# 13_LMS3_Power.net
KiCad netlist of a schematic drawn in Altium Designer
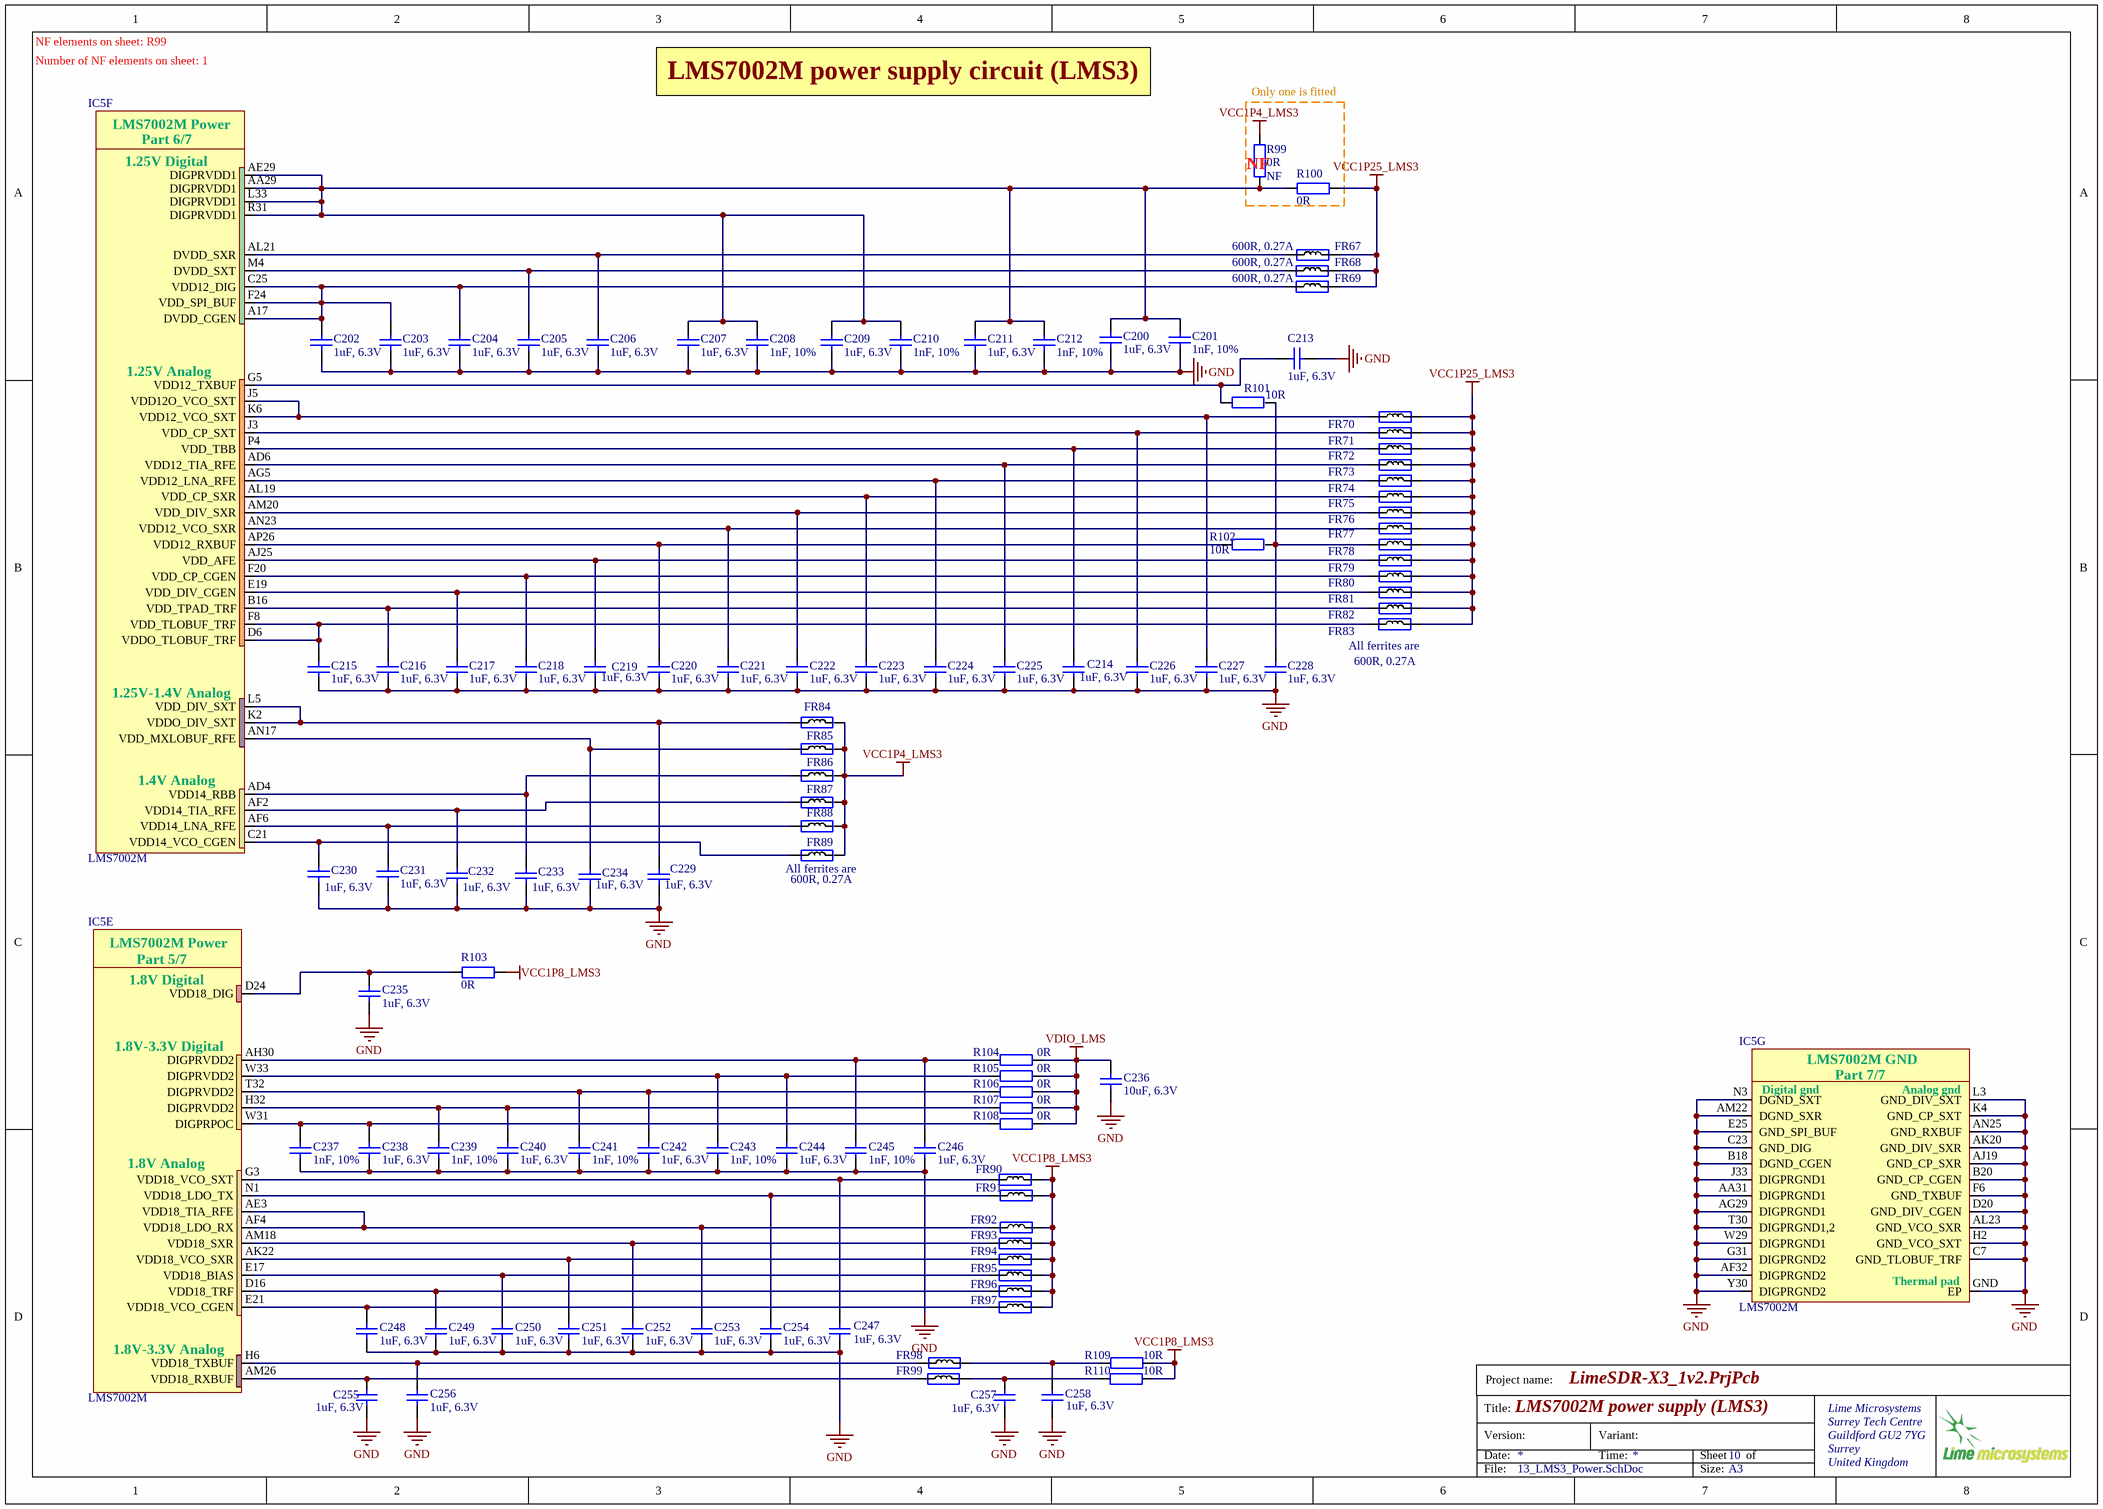
[diagram p0: 13_LMS3_Power.SchDoc]

(export (version "E")
  (design (tool "Eeschema 10.0.6"))
  (components
    (comp (ref "C200")
      (value "1uF, 6.3V")
      (footprint "CAP0201")
      (fields (field (name "TOLERANCE") "±20%") (field (name "MANUFACTURER") "TDK Corporation"))
      (libsource (lib "") (part "Cap_0402_2"))
    )
    (comp (ref "C201")
      (value "1nF, 10%")
      (footprint "CAP0201")
      (fields (field (name "TOLERANCE") "±10%") (field (name "MANUFACTURER") "TDK Corporation"))
      (libsource (lib "") (part "Cap_0402_2"))
    )
    (comp (ref "C202")
      (value "1uF, 6.3V")
      (footprint "CAP0201")
      (fields (field (name "TOLERANCE") "±20%") (field (name "MANUFACTURER") "TDK Corporation"))
      (libsource (lib "") (part "Cap_0402_1"))
    )
    (comp (ref "C203")
      (value "1uF, 6.3V")
      (footprint "CAP0201")
      (fields (field (name "TOLERANCE") "±20%") (field (name "MANUFACTURER") "TDK Corporation"))
      (libsource (lib "") (part "Cap_0402_1"))
    )
    (comp (ref "C204")
      (value "1uF, 6.3V")
      (footprint "CAP0201")
      (fields (field (name "TOLERANCE") "±20%") (field (name "MANUFACTURER") "TDK Corporation"))
      (libsource (lib "") (part "Cap_0402_1"))
    )
    (comp (ref "C205")
      (value "1uF, 6.3V")
      (footprint "CAP0201")
      (fields (field (name "TOLERANCE") "±20%") (field (name "MANUFACTURER") "TDK Corporation"))
      (libsource (lib "") (part "Cap_0402_2"))
    )
    (comp (ref "C206")
      (value "1uF, 6.3V")
      (footprint "CAP0201")
      (fields (field (name "TOLERANCE") "±20%") (field (name "MANUFACTURER") "TDK Corporation"))
      (libsource (lib "") (part "Cap_0402_1"))
    )
    (comp (ref "C207")
      (value "1uF, 6.3V")
      (footprint "CAP0201")
      (fields (field (name "TOLERANCE") "±20%") (field (name "MANUFACTURER") "TDK Corporation"))
      (libsource (lib "") (part "Cap_0402_2"))
    )
    (comp (ref "C208")
      (value "1nF, 10%")
      (footprint "CAP0201")
      (fields (field (name "TOLERANCE") "±10%") (field (name "MANUFACTURER") "TDK Corporation"))
      (libsource (lib "") (part "Cap_0402_2"))
    )
    (comp (ref "C209")
      (value "1uF, 6.3V")
      (footprint "CAP0201")
      (fields (field (name "TOLERANCE") "±20%") (field (name "MANUFACTURER") "TDK Corporation"))
      (libsource (lib "") (part "Cap_0402_2"))
    )
    (comp (ref "C210")
      (value "1nF, 10%")
      (footprint "CAP0201")
      (fields (field (name "TOLERANCE") "±10%") (field (name "MANUFACTURER") "TDK Corporation"))
      (libsource (lib "") (part "Cap_0402_2"))
    )
    (comp (ref "C211")
      (value "1uF, 6.3V")
      (footprint "CAP0201")
      (fields (field (name "TOLERANCE") "±20%") (field (name "MANUFACTURER") "TDK Corporation"))
      (libsource (lib "") (part "Cap_0402_2"))
    )
    (comp (ref "C212")
      (value "1nF, 10%")
      (footprint "CAP0201")
      (fields (field (name "TOLERANCE") "±10%") (field (name "MANUFACTURER") "TDK Corporation"))
      (libsource (lib "") (part "Cap_0402_2"))
    )
    (comp (ref "C213")
      (value "1uF, 6.3V")
      (footprint "CAP0201")
      (fields (field (name "TOLERANCE") "±20%") (field (name "MANUFACTURER") "TDK Corporation"))
      (libsource (lib "") (part "Cap_0402_4"))
    )
    (comp (ref "C214")
      (value "1uF, 6.3V")
      (footprint "CAP0201")
      (fields (field (name "TOLERANCE") "±20%") (field (name "MANUFACTURER") "TDK Corporation"))
      (libsource (lib "") (part "Cap_0402_1"))
    )
    (comp (ref "C215")
      (value "1uF, 6.3V")
      (footprint "CAP0201")
      (fields (field (name "TOLERANCE") "±20%") (field (name "MANUFACTURER") "TDK Corporation"))
      (libsource (lib "") (part "Cap_0402_1"))
    )
    (comp (ref "C216")
      (value "1uF, 6.3V")
      (footprint "CAP0201")
      (fields (field (name "TOLERANCE") "±20%") (field (name "MANUFACTURER") "TDK Corporation"))
      (libsource (lib "") (part "Cap_0402_1"))
    )
    (comp (ref "C217")
      (value "1uF, 6.3V")
      (footprint "CAP0201")
      (fields (field (name "TOLERANCE") "±20%") (field (name "MANUFACTURER") "TDK Corporation"))
      (libsource (lib "") (part "Cap_0402_1"))
    )
    (comp (ref "C218")
      (value "1uF, 6.3V")
      (footprint "CAP0201")
      (fields (field (name "TOLERANCE") "±20%") (field (name "MANUFACTURER") "TDK Corporation"))
      (libsource (lib "") (part "Cap_0402_2"))
    )
    (comp (ref "C219")
      (value "1uF, 6.3V")
      (footprint "CAP0201")
      (fields (field (name "TOLERANCE") "±20%") (field (name "MANUFACTURER") "TDK Corporation"))
      (libsource (lib "") (part "Cap_0402_1"))
    )
    (comp (ref "C220")
      (value "1uF, 6.3V")
      (footprint "CAP0201")
      (fields (field (name "TOLERANCE") "±20%") (field (name "MANUFACTURER") "TDK Corporation"))
      (libsource (lib "") (part "Cap_0402_1"))
    )
    (comp (ref "C221")
      (value "1uF, 6.3V")
      (footprint "CAP0201")
      (fields (field (name "TOLERANCE") "±20%") (field (name "MANUFACTURER") "TDK Corporation"))
      (libsource (lib "") (part "Cap_0402_1"))
    )
    (comp (ref "C222")
      (value "1uF, 6.3V")
      (footprint "CAP0201")
      (fields (field (name "TOLERANCE") "±20%") (field (name "MANUFACTURER") "TDK Corporation"))
      (libsource (lib "") (part "Cap_0402_1"))
    )
    (comp (ref "C223")
      (value "1uF, 6.3V")
      (footprint "CAP0201")
      (fields (field (name "TOLERANCE") "±20%") (field (name "MANUFACTURER") "TDK Corporation"))
      (libsource (lib "") (part "Cap_0402_1"))
    )
    (comp (ref "C224")
      (value "1uF, 6.3V")
      (footprint "CAP0201")
      (fields (field (name "TOLERANCE") "±20%") (field (name "MANUFACTURER") "TDK Corporation"))
      (libsource (lib "") (part "Cap_0402_1"))
    )
    (comp (ref "C225")
      (value "1uF, 6.3V")
      (footprint "CAP0201")
      (fields (field (name "TOLERANCE") "±20%") (field (name "MANUFACTURER") "TDK Corporation"))
      (libsource (lib "") (part "Cap_0402_2"))
    )
    (comp (ref "C226")
      (value "1uF, 6.3V")
      (footprint "CAP0201")
      (fields (field (name "TOLERANCE") "±20%") (field (name "MANUFACTURER") "TDK Corporation"))
      (libsource (lib "") (part "Cap_0402_1"))
    )
    (comp (ref "C227")
      (value "1uF, 6.3V")
      (footprint "CAP0201")
      (fields (field (name "TOLERANCE") "±20%") (field (name "MANUFACTURER") "TDK Corporation"))
      (libsource (lib "") (part "Cap_0402_2"))
    )
    (comp (ref "C228")
      (value "1uF, 6.3V")
      (footprint "CAP0201")
      (fields (field (name "TOLERANCE") "±20%") (field (name "MANUFACTURER") "TDK Corporation"))
      (libsource (lib "") (part "Cap_0402_2"))
    )
    (comp (ref "C229")
      (value "1uF, 6.3V")
      (footprint "CAP0201")
      (fields (field (name "TOLERANCE") "±20%") (field (name "MANUFACTURER") "TDK Corporation"))
      (libsource (lib "") (part "Cap_0402_1"))
    )
    (comp (ref "C230")
      (value "1uF, 6.3V")
      (footprint "CAP0201")
      (fields (field (name "TOLERANCE") "±20%") (field (name "MANUFACTURER") "TDK Corporation"))
      (libsource (lib "") (part "Cap_0402_1"))
    )
    (comp (ref "C231")
      (value "1uF, 6.3V")
      (footprint "CAP0201")
      (fields (field (name "TOLERANCE") "±20%") (field (name "MANUFACTURER") "TDK Corporation"))
      (libsource (lib "") (part "Cap_0402_1"))
    )
    (comp (ref "C232")
      (value "1uF, 6.3V")
      (footprint "CAP0201")
      (fields (field (name "TOLERANCE") "±20%") (field (name "MANUFACTURER") "TDK Corporation"))
      (libsource (lib "") (part "Cap_0402_3"))
    )
    (comp (ref "C233")
      (value "1uF, 6.3V")
      (footprint "CAP0201")
      (fields (field (name "TOLERANCE") "±20%") (field (name "MANUFACTURER") "TDK Corporation"))
      (libsource (lib "") (part "Cap_0402_3"))
    )
    (comp (ref "C234")
      (value "1uF, 6.3V")
      (footprint "CAP0201")
      (fields (field (name "TOLERANCE") "±20%") (field (name "MANUFACTURER") "TDK Corporation"))
      (libsource (lib "") (part "Cap_0402_1"))
    )
    (comp (ref "C235")
      (value "1uF, 6.3V")
      (footprint "CAP0201")
      (fields (field (name "TOLERANCE") "±20%") (field (name "MANUFACTURER") "TDK Corporation"))
      (libsource (lib "LimeMicroAltiumLib_schLib") (part "Cap_0402"))
    )
    (comp (ref "C236")
      (value "10uF, 6.3V")
      (footprint "CAP0603")
      (fields (field (name "TOLERANCE") "±20%") (field (name "MANUFACTURER") "Yageo"))
      (libsource (lib "LimeFPGAboard_schLib") (part "Cap_0603"))
    )
    (comp (ref "C237")
      (value "1nF, 10%")
      (footprint "CAP0201")
      (fields (field (name "TOLERANCE") "±10%") (field (name "MANUFACTURER") "TDK Corporation"))
      (libsource (lib "LimeMicroAltiumLib_schLib") (part "Cap_0402"))
    )
    (comp (ref "C238")
      (value "1uF, 6.3V")
      (footprint "CAP0201")
      (fields (field (name "TOLERANCE") "±20%") (field (name "MANUFACTURER") "TDK Corporation"))
      (libsource (lib "LimeMicroAltiumLib_schLib") (part "Cap_0402"))
    )
    (comp (ref "C239")
      (value "1nF, 10%")
      (footprint "CAP0201")
      (fields (field (name "TOLERANCE") "±10%") (field (name "MANUFACTURER") "TDK Corporation"))
      (libsource (lib "LimeMicroAltiumLib_schLib") (part "Cap_0402"))
    )
    (comp (ref "C240")
      (value "1uF, 6.3V")
      (footprint "CAP0201")
      (fields (field (name "TOLERANCE") "±20%") (field (name "MANUFACTURER") "TDK Corporation"))
      (libsource (lib "LimeMicroAltiumLib_schLib") (part "Cap_0402"))
    )
    (comp (ref "C241")
      (value "1nF, 10%")
      (footprint "CAP0201")
      (fields (field (name "TOLERANCE") "±10%") (field (name "MANUFACTURER") "TDK Corporation"))
      (libsource (lib "LimeMicroAltiumLib_schLib") (part "Cap_0402"))
    )
    (comp (ref "C242")
      (value "1uF, 6.3V")
      (footprint "CAP0201")
      (fields (field (name "TOLERANCE") "±20%") (field (name "MANUFACTURER") "TDK Corporation"))
      (libsource (lib "LimeMicroAltiumLib_schLib") (part "Cap_0402"))
    )
    (comp (ref "C243")
      (value "1nF, 10%")
      (footprint "CAP0201")
      (fields (field (name "TOLERANCE") "±10%") (field (name "MANUFACTURER") "TDK Corporation"))
      (libsource (lib "LimeMicroAltiumLib_schLib") (part "Cap_0402"))
    )
    (comp (ref "C244")
      (value "1uF, 6.3V")
      (footprint "CAP0201")
      (fields (field (name "TOLERANCE") "±20%") (field (name "MANUFACTURER") "TDK Corporation"))
      (libsource (lib "LimeMicroAltiumLib_schLib") (part "Cap_0402"))
    )
    (comp (ref "C245")
      (value "1nF, 10%")
      (footprint "CAP0201")
      (fields (field (name "TOLERANCE") "±10%") (field (name "MANUFACTURER") "TDK Corporation"))
      (libsource (lib "LimeMicroAltiumLib_schLib") (part "Cap_0402"))
    )
    (comp (ref "C246")
      (value "1uF, 6.3V")
      (footprint "CAP0201")
      (fields (field (name "TOLERANCE") "±20%") (field (name "MANUFACTURER") "TDK Corporation"))
      (libsource (lib "LimeMicroAltiumLib_schLib") (part "Cap_0402"))
    )
    (comp (ref "C247")
      (value "1uF, 6.3V")
      (footprint "CAP0201")
      (fields (field (name "TOLERANCE") "±20%") (field (name "MANUFACTURER") "TDK Corporation"))
      (libsource (lib "LimeMicroAltiumLib_schLib") (part "Cap_0402"))
    )
    (comp (ref "C248")
      (value "1uF, 6.3V")
      (footprint "CAP0201")
      (fields (field (name "TOLERANCE") "±20%") (field (name "MANUFACTURER") "TDK Corporation"))
      (libsource (lib "LimeMicroAltiumLib_schLib") (part "Cap_0402"))
    )
    (comp (ref "C249")
      (value "1uF, 6.3V")
      (footprint "CAP0201")
      (fields (field (name "TOLERANCE") "±20%") (field (name "MANUFACTURER") "TDK Corporation"))
      (libsource (lib "LimeMicroAltiumLib_schLib") (part "Cap_0402"))
    )
    (comp (ref "C250")
      (value "1uF, 6.3V")
      (footprint "CAP0201")
      (fields (field (name "TOLERANCE") "±20%") (field (name "MANUFACTURER") "TDK Corporation"))
      (libsource (lib "LimeMicroAltiumLib_schLib") (part "Cap_0402"))
    )
    (comp (ref "C251")
      (value "1uF, 6.3V")
      (footprint "CAP0201")
      (fields (field (name "TOLERANCE") "±20%") (field (name "MANUFACTURER") "TDK Corporation"))
      (libsource (lib "LimeMicroAltiumLib_schLib") (part "Cap_0402"))
    )
    (comp (ref "C252")
      (value "1uF, 6.3V")
      (footprint "CAP0201")
      (fields (field (name "TOLERANCE") "±20%") (field (name "MANUFACTURER") "TDK Corporation"))
      (libsource (lib "LimeMicroAltiumLib_schLib") (part "Cap_0402"))
    )
    (comp (ref "C253")
      (value "1uF, 6.3V")
      (footprint "CAP0201")
      (fields (field (name "TOLERANCE") "±20%") (field (name "MANUFACTURER") "TDK Corporation"))
      (libsource (lib "LimeMicroAltiumLib_schLib") (part "Cap_0402"))
    )
    (comp (ref "C254")
      (value "1uF, 6.3V")
      (footprint "CAP0201")
      (fields (field (name "TOLERANCE") "±20%") (field (name "MANUFACTURER") "TDK Corporation"))
      (libsource (lib "LimeMicroAltiumLib_schLib") (part "Cap_0402"))
    )
    (comp (ref "C255")
      (value "1uF, 6.3V")
      (footprint "CAP0201")
      (fields (field (name "TOLERANCE") "±20%") (field (name "MANUFACTURER") "TDK Corporation"))
      (libsource (lib "LimeMicroAltiumLib_schLib") (part "Cap_0402"))
    )
    (comp (ref "C256")
      (value "1uF, 6.3V")
      (footprint "CAP0201")
      (fields (field (name "TOLERANCE") "±20%") (field (name "MANUFACTURER") "TDK Corporation"))
      (libsource (lib "LimeMicroAltiumLib_schLib") (part "Cap_0402"))
    )
    (comp (ref "C257")
      (value "1uF, 6.3V")
      (footprint "CAP0201")
      (fields (field (name "TOLERANCE") "±20%") (field (name "MANUFACTURER") "TDK Corporation"))
      (libsource (lib "LimeMicroAltiumLib_schLib") (part "Cap_0402"))
    )
    (comp (ref "C258")
      (value "1uF, 6.3V")
      (footprint "CAP0201")
      (fields (field (name "TOLERANCE") "±20%") (field (name "MANUFACTURER") "TDK Corporation"))
      (libsource (lib "LimeMicroAltiumLib_schLib") (part "Cap_0402"))
    )
    (comp (ref "FR67")
      (value "600R, 0.27A")
      (footprint "RES0201")
      (fields (field (name "MANUFACTURER") "Taiyo Yuden"))
      (libsource (lib "") (part "Ferrite_1"))
    )
    (comp (ref "FR68")
      (value "600R, 0.27A")
      (footprint "RES0201")
      (fields (field (name "MANUFACTURER") "Taiyo Yuden"))
      (libsource (lib "LimeMicroAltiumLib_schLib") (part "Ferrite"))
    )
    (comp (ref "FR69")
      (value "600R, 0.27A")
      (footprint "RES0201")
      (fields (field (name "MANUFACTURER") "Taiyo Yuden"))
      (libsource (lib "LimeMicroAltiumLib_schLib") (part "Ferrite"))
    )
    (comp (ref "FR70")
      (value "600R, 0.27A")
      (footprint "RES0201")
      (fields (field (name "MANUFACTURER") "Taiyo Yuden"))
      (libsource (lib "") (part "Ferrite_1"))
    )
    (comp (ref "FR71")
      (value "600R, 0.27A")
      (footprint "RES0201")
      (fields (field (name "MANUFACTURER") "Taiyo Yuden"))
      (libsource (lib "") (part "Ferrite_1"))
    )
    (comp (ref "FR72")
      (value "600R, 0.27A")
      (footprint "RES0201")
      (fields (field (name "MANUFACTURER") "Taiyo Yuden"))
      (libsource (lib "") (part "Ferrite_1"))
    )
    (comp (ref "FR73")
      (value "600R, 0.27A")
      (footprint "RES0201")
      (fields (field (name "MANUFACTURER") "Taiyo Yuden"))
      (libsource (lib "") (part "Ferrite_1"))
    )
    (comp (ref "FR74")
      (value "600R, 0.27A")
      (footprint "RES0201")
      (fields (field (name "MANUFACTURER") "Taiyo Yuden"))
      (libsource (lib "") (part "Ferrite_1"))
    )
    (comp (ref "FR75")
      (value "600R, 0.27A")
      (footprint "RES0201")
      (fields (field (name "MANUFACTURER") "Taiyo Yuden"))
      (libsource (lib "") (part "Ferrite_1"))
    )
    (comp (ref "FR76")
      (value "600R, 0.27A")
      (footprint "RES0201")
      (fields (field (name "MANUFACTURER") "Taiyo Yuden"))
      (libsource (lib "") (part "Ferrite_1"))
    )
    (comp (ref "FR77")
      (value "600R, 0.27A")
      (footprint "RES0201")
      (fields (field (name "MANUFACTURER") "Taiyo Yuden"))
      (libsource (lib "") (part "Ferrite_1"))
    )
    (comp (ref "FR78")
      (value "600R, 0.27A")
      (footprint "RES0201")
      (fields (field (name "MANUFACTURER") "Taiyo Yuden"))
      (libsource (lib "") (part "Ferrite_1"))
    )
    (comp (ref "FR79")
      (value "600R, 0.27A")
      (footprint "RES0201")
      (fields (field (name "MANUFACTURER") "Taiyo Yuden"))
      (libsource (lib "") (part "Ferrite_1"))
    )
    (comp (ref "FR80")
      (value "600R, 0.27A")
      (footprint "RES0201")
      (fields (field (name "MANUFACTURER") "Taiyo Yuden"))
      (libsource (lib "") (part "Ferrite_1"))
    )
    (comp (ref "FR81")
      (value "600R, 0.27A")
      (footprint "RES0201")
      (fields (field (name "MANUFACTURER") "Taiyo Yuden"))
      (libsource (lib "") (part "Ferrite_1"))
    )
    (comp (ref "FR82")
      (value "600R, 0.27A")
      (footprint "RES0201")
      (fields (field (name "MANUFACTURER") "Taiyo Yuden"))
      (libsource (lib "") (part "Ferrite_1"))
    )
    (comp (ref "FR83")
      (value "600R, 0.27A")
      (footprint "RES0201")
      (fields (field (name "MANUFACTURER") "Taiyo Yuden"))
      (libsource (lib "LimeMicroAltiumLib_schLib") (part "Ferrite"))
    )
    (comp (ref "FR84")
      (value "600R, 0.27A")
      (footprint "RES0201")
      (fields (field (name "MANUFACTURER") "Taiyo Yuden"))
      (libsource (lib "LimeMicroAltiumLib_schLib") (part "Ferrite"))
    )
    (comp (ref "FR85")
      (value "600R, 0.27A")
      (footprint "RES0201")
      (fields (field (name "MANUFACTURER") "Taiyo Yuden"))
      (libsource (lib "LimeMicroAltiumLib_schLib") (part "Ferrite"))
    )
    (comp (ref "FR86")
      (value "600R, 0.27A")
      (footprint "RES0201")
      (fields (field (name "MANUFACTURER") "Taiyo Yuden"))
      (libsource (lib "LimeMicroAltiumLib_schLib") (part "Ferrite"))
    )
    (comp (ref "FR87")
      (value "600R, 0.27A")
      (footprint "RES0201")
      (fields (field (name "MANUFACTURER") "Taiyo Yuden"))
      (libsource (lib "LimeMicroAltiumLib_schLib") (part "Ferrite"))
    )
    (comp (ref "FR88")
      (value "600R, 0.27A")
      (footprint "RES0201")
      (fields (field (name "MANUFACTURER") "Taiyo Yuden"))
      (libsource (lib "LimeMicroAltiumLib_schLib") (part "Ferrite"))
    )
    (comp (ref "FR89")
      (value "600R, 0.27A")
      (footprint "RES0201")
      (fields (field (name "MANUFACTURER") "Taiyo Yuden"))
      (libsource (lib "LimeMicroAltiumLib_schLib") (part "Ferrite"))
    )
    (comp (ref "FR90")
      (value "600R, 0.27A")
      (footprint "RES0201")
      (fields (field (name "MANUFACTURER") "Taiyo Yuden"))
      (libsource (lib "LimeMicroAltiumLib_schLib") (part "Ferrite"))
    )
    (comp (ref "FR91")
      (value "600R, 0.27A")
      (footprint "RES0201")
      (fields (field (name "MANUFACTURER") "Taiyo Yuden"))
      (libsource (lib "") (part "Ferrite_2"))
    )
    (comp (ref "FR92")
      (value "600R, 0.27A")
      (footprint "RES0201")
      (fields (field (name "MANUFACTURER") "Taiyo Yuden"))
      (libsource (lib "") (part "Ferrite_2"))
    )
    (comp (ref "FR93")
      (value "600R, 0.27A")
      (footprint "RES0201")
      (fields (field (name "MANUFACTURER") "Taiyo Yuden"))
      (libsource (lib "LimeMicroAltiumLib_schLib") (part "Ferrite"))
    )
    (comp (ref "FR94")
      (value "600R, 0.27A")
      (footprint "RES0201")
      (fields (field (name "MANUFACTURER") "Taiyo Yuden"))
      (libsource (lib "LimeMicroAltiumLib_schLib") (part "Ferrite"))
    )
    (comp (ref "FR95")
      (value "600R, 0.27A")
      (footprint "RES0201")
      (fields (field (name "MANUFACTURER") "Taiyo Yuden"))
      (libsource (lib "LimeMicroAltiumLib_schLib") (part "Ferrite"))
    )
    (comp (ref "FR96")
      (value "600R, 0.27A")
      (footprint "RES0201")
      (fields (field (name "MANUFACTURER") "Taiyo Yuden"))
      (libsource (lib "LimeMicroAltiumLib_schLib") (part "Ferrite"))
    )
    (comp (ref "FR97")
      (value "600R, 0.27A")
      (footprint "RES0201")
      (fields (field (name "MANUFACTURER") "Taiyo Yuden"))
      (libsource (lib "LimeMicroAltiumLib_schLib") (part "Ferrite"))
    )
    (comp (ref "FR98")
      (value "600R, 0.27A")
      (footprint "RES0201")
      (fields (field (name "MANUFACTURER") "Taiyo Yuden"))
      (libsource (lib "") (part "Ferrite_2"))
    )
    (comp (ref "FR99")
      (value "600R, 0.27A")
      (footprint "RES0201")
      (fields (field (name "MANUFACTURER") "Taiyo Yuden"))
      (libsource (lib "LimeMicroAltiumLib_schLib") (part "Ferrite"))
    )
    (comp (ref "IC5")
      (value "LMS7002M")
      (footprint "LMS7002M_v5")
      (description "Schematic symbol revision 4. Default footprint - 0.31mm pad")
      (fields (field (name "MANUFACTURER") "Lime Microsystems"))
      (libsource (lib "LimeMicroAltiumLib_schLib_r04") (part "LMS7002Mr4"))
    )
    (comp (ref "R99")
      (value "0R")
      (footprint "RES0402")
      (fields
        (field (name "ASSEMBLY INFO") "NF")
        (field (name "MANUFACTURER") "Yageo")
        (field (name "TOLERANCE") "Jumper")
      )
      (libsource (lib "LimeMicroAltiumLib_schLib") (part "Res_0402"))
    )
    (comp (ref "R100")
      (value "0R")
      (footprint "RES0402")
      (fields (field (name "MANUFACTURER") "Yageo") (field (name "TOLERANCE") "Jumper"))
      (libsource (lib "") (part "Res_0402_1"))
    )
    (comp (ref "R101")
      (value "10R")
      (footprint "RES0201")
      (fields
        (field (name "MANUFACTURER") "Panasonic Electronic Components")
        (field (name "TOLERANCE") "±1%")
      )
      (libsource (lib "LimeMicroAltiumLib_schLib") (part "Res_0402"))
    )
    (comp (ref "R102")
      (value "10R")
      (footprint "RES0201")
      (fields
        (field (name "MANUFACTURER") "Panasonic Electronic Components")
        (field (name "TOLERANCE") "±1%")
      )
      (libsource (lib "LimeMicroAltiumLib_schLib") (part "Res_0402"))
    )
    (comp (ref "R103")
      (value "0R")
      (footprint "RES0201")
      (fields (field (name "MANUFACTURER") "Rohm Semiconductor") (field (name "TOLERANCE") "Jumper"))
      (libsource (lib "LimeMicroAltiumLib_schLib") (part "Res_0402"))
    )
    (comp (ref "R104")
      (value "0R")
      (footprint "RES0402")
      (fields (field (name "MANUFACTURER") "Yageo") (field (name "TOLERANCE") "Jumper"))
      (libsource (lib "LimeMicroAltiumLib_schLib") (part "Res_0402"))
    )
    (comp (ref "R105")
      (value "0R")
      (footprint "RES0402")
      (fields (field (name "MANUFACTURER") "Yageo") (field (name "TOLERANCE") "Jumper"))
      (libsource (lib "LimeMicroAltiumLib_schLib") (part "Res_0402"))
    )
    (comp (ref "R106")
      (value "0R")
      (footprint "RES0402")
      (fields (field (name "MANUFACTURER") "Yageo") (field (name "TOLERANCE") "Jumper"))
      (libsource (lib "LimeMicroAltiumLib_schLib") (part "Res_0402"))
    )
    (comp (ref "R107")
      (value "0R")
      (footprint "RES0402")
      (fields (field (name "MANUFACTURER") "Yageo") (field (name "TOLERANCE") "Jumper"))
      (libsource (lib "LimeMicroAltiumLib_schLib") (part "Res_0402"))
    )
    (comp (ref "R108")
      (value "0R")
      (footprint "RES0402")
      (fields (field (name "MANUFACTURER") "Yageo") (field (name "TOLERANCE") "Jumper"))
      (libsource (lib "LimeMicroAltiumLib_schLib") (part "Res_0402"))
    )
    (comp (ref "R109")
      (value "10R")
      (footprint "RES0201")
      (fields
        (field (name "MANUFACTURER") "Panasonic Electronic Components")
        (field (name "TOLERANCE") "±1%")
      )
      (libsource (lib "LimeMicroAltiumLib_schLib") (part "Res_0402"))
    )
    (comp (ref "R110")
      (value "10R")
      (footprint "RES0201")
      (fields
        (field (name "MANUFACTURER") "Panasonic Electronic Components")
        (field (name "TOLERANCE") "±1%")
      )
      (libsource (lib "LimeMicroAltiumLib_schLib") (part "Res_0402"))
    )
  )
  (nets
    (net (code "1") (name "GND") (class "Default")
      (node (ref "C200") (pin "2") (pinfunction "2_2") (pintype "passive"))
      (node (ref "C201") (pin "2") (pinfunction "2_2") (pintype "passive"))
      (node (ref "C202") (pin "2") (pinfunction "2_2") (pintype "passive"))
      (node (ref "C203") (pin "2") (pinfunction "2_2") (pintype "passive"))
      (node (ref "C204") (pin "2") (pinfunction "2_2") (pintype "passive"))
      (node (ref "C205") (pin "1") (pinfunction "1_1") (pintype "passive"))
      (node (ref "C206") (pin "2") (pinfunction "2_2") (pintype "passive"))
      (node (ref "C207") (pin "2") (pinfunction "2_2") (pintype "passive"))
      (node (ref "C208") (pin "2") (pinfunction "2_2") (pintype "passive"))
      (node (ref "C209") (pin "2") (pinfunction "2_2") (pintype "passive"))
      (node (ref "C210") (pin "2") (pinfunction "2_2") (pintype "passive"))
      (node (ref "C211") (pin "2") (pinfunction "2_2") (pintype "passive"))
      (node (ref "C212") (pin "2") (pinfunction "2_2") (pintype "passive"))
      (node (ref "C213") (pin "2") (pinfunction "2_2") (pintype "passive"))
      (node (ref "C214") (pin "2") (pinfunction "2_2") (pintype "passive"))
      (node (ref "C215") (pin "2") (pinfunction "2_2") (pintype "passive"))
      (node (ref "C216") (pin "2") (pinfunction "2_2") (pintype "passive"))
      (node (ref "C217") (pin "2") (pinfunction "2_2") (pintype "passive"))
      (node (ref "C218") (pin "1") (pinfunction "1_1") (pintype "passive"))
      (node (ref "C219") (pin "2") (pinfunction "2_2") (pintype "passive"))
      (node (ref "C220") (pin "2") (pinfunction "2_2") (pintype "passive"))
      (node (ref "C221") (pin "2") (pinfunction "2_2") (pintype "passive"))
      (node (ref "C222") (pin "2") (pinfunction "2_2") (pintype "passive"))
      (node (ref "C223") (pin "2") (pinfunction "2_2") (pintype "passive"))
      (node (ref "C224") (pin "2") (pinfunction "2_2") (pintype "passive"))
      (node (ref "C225") (pin "1") (pinfunction "1_1") (pintype "passive"))
      (node (ref "C226") (pin "2") (pinfunction "2_2") (pintype "passive"))
      (node (ref "C227") (pin "1") (pinfunction "1_1") (pintype "passive"))
      (node (ref "C228") (pin "1") (pinfunction "1_1") (pintype "passive"))
      (node (ref "C229") (pin "2") (pinfunction "2_2") (pintype "passive"))
      (node (ref "C230") (pin "2") (pinfunction "2_2") (pintype "passive"))
      (node (ref "C231") (pin "2") (pinfunction "2_2") (pintype "passive"))
      (node (ref "C232") (pin "2") (pinfunction "2_2") (pintype "passive"))
      (node (ref "C233") (pin "2") (pinfunction "2_2") (pintype "passive"))
      (node (ref "C234") (pin "2") (pinfunction "2_2") (pintype "passive"))
      (node (ref "C235") (pin "2") (pinfunction "2_2") (pintype "passive"))
      (node (ref "C236") (pin "1") (pinfunction "1_1") (pintype "passive"))
      (node (ref "C237") (pin "2") (pinfunction "2_2") (pintype "passive"))
      (node (ref "C238") (pin "2") (pinfunction "2_2") (pintype "passive"))
      (node (ref "C239") (pin "2") (pinfunction "2_2") (pintype "passive"))
      (node (ref "C240") (pin "2") (pinfunction "2_2") (pintype "passive"))
      (node (ref "C241") (pin "2") (pinfunction "2_2") (pintype "passive"))
      (node (ref "C242") (pin "2") (pinfunction "2_2") (pintype "passive"))
      (node (ref "C243") (pin "2") (pinfunction "2_2") (pintype "passive"))
      (node (ref "C244") (pin "2") (pinfunction "2_2") (pintype "passive"))
      (node (ref "C245") (pin "2") (pinfunction "2_2") (pintype "passive"))
      (node (ref "C246") (pin "2") (pinfunction "2_2") (pintype "passive"))
      (node (ref "C247") (pin "2") (pinfunction "2_2") (pintype "passive"))
      (node (ref "C248") (pin "2") (pinfunction "2_2") (pintype "passive"))
      (node (ref "C249") (pin "2") (pinfunction "2_2") (pintype "passive"))
      (node (ref "C250") (pin "2") (pinfunction "2_2") (pintype "passive"))
      (node (ref "C251") (pin "2") (pinfunction "2_2") (pintype "passive"))
      (node (ref "C252") (pin "2") (pinfunction "2_2") (pintype "passive"))
      (node (ref "C253") (pin "2") (pinfunction "2_2") (pintype "passive"))
      (node (ref "C254") (pin "2") (pinfunction "2_2") (pintype "passive"))
      (node (ref "C255") (pin "2") (pinfunction "2_2") (pintype "passive"))
      (node (ref "C256") (pin "2") (pinfunction "2_2") (pintype "passive"))
      (node (ref "C257") (pin "2") (pinfunction "2_2") (pintype "passive"))
      (node (ref "C258") (pin "2") (pinfunction "2_2") (pintype "passive"))
      (node (ref "IC5") (pin "AA31") (pinfunction "DIGPRGND1_AA31") (pintype "passive"))
      (node (ref "IC5") (pin "AF32") (pinfunction "DIGPRGND2_AF32") (pintype "passive"))
      (node (ref "IC5") (pin "AG29") (pinfunction "DIGPRGND1_AG29") (pintype "passive"))
      (node (ref "IC5") (pin "AJ19") (pinfunction "GND_CP_SXR_AJ19") (pintype "passive"))
      (node (ref "IC5") (pin "AK20") (pinfunction "GND_DIV_SXR_AK20") (pintype "passive"))
      (node (ref "IC5") (pin "AL23") (pinfunction "GND_VCO_SXR_AL23") (pintype "passive"))
      (node (ref "IC5") (pin "AM22") (pinfunction "DGND_SXR_AM22") (pintype "passive"))
      (node (ref "IC5") (pin "AN25") (pinfunction "GND_RXBUF_AN25") (pintype "passive"))
      (node (ref "IC5") (pin "B18") (pinfunction "DGND_CGEN_B18") (pintype "passive"))
      (node (ref "IC5") (pin "B20") (pinfunction "GND_CP_CGEN_B20") (pintype "passive"))
      (node (ref "IC5") (pin "C23") (pinfunction "GND_DIG_C23") (pintype "passive"))
      (node (ref "IC5") (pin "C7") (pinfunction "GND_TLOBUF_TRF_C7") (pintype "passive"))
      (node (ref "IC5") (pin "D20") (pinfunction "GND_DIV_CGEN_D20") (pintype "passive"))
      (node (ref "IC5") (pin "E25") (pinfunction "GND_SPI_BUF_E25") (pintype "passive"))
      (node (ref "IC5") (pin "F6") (pinfunction "GND_TXBUF_F6") (pintype "passive"))
      (node (ref "IC5") (pin "G31") (pinfunction "DIGPRGND2_G31") (pintype "passive"))
      (node (ref "IC5") (pin "GND") (pinfunction "EP_GND") (pintype "passive"))
      (node (ref "IC5") (pin "H2") (pinfunction "GND_VCO_SXT_H2") (pintype "passive"))
      (node (ref "IC5") (pin "J33") (pinfunction "DIGPRGND1_J33") (pintype "passive"))
      (node (ref "IC5") (pin "K4") (pinfunction "GND_CP_SXT_K4") (pintype "passive"))
      (node (ref "IC5") (pin "L3") (pinfunction "GND_DIV_SXT_L3") (pintype "passive"))
      (node (ref "IC5") (pin "N3") (pinfunction "DGND_SXT_N3") (pintype "passive"))
      (node (ref "IC5") (pin "T30") (pinfunction "DIGPRGND1,2_T30") (pintype "passive"))
      (node (ref "IC5") (pin "W29") (pinfunction "DIGPRGND1_W29") (pintype "passive"))
      (node (ref "IC5") (pin "Y30") (pinfunction "DIGPRGND2_Y30") (pintype "passive"))
    )
    (net (code "2") (name "Net-(C200-Pad1)") (class "Default")
      (node (ref "C200") (pin "1") (pinfunction "1_1") (pintype "passive"))
      (node (ref "C201") (pin "1") (pinfunction "1_1") (pintype "passive"))
      (node (ref "C207") (pin "1") (pinfunction "1_1") (pintype "passive"))
      (node (ref "C208") (pin "1") (pinfunction "1_1") (pintype "passive"))
      (node (ref "C209") (pin "1") (pinfunction "1_1") (pintype "passive"))
      (node (ref "C210") (pin "1") (pinfunction "1_1") (pintype "passive"))
      (node (ref "C211") (pin "1") (pinfunction "1_1") (pintype "passive"))
      (node (ref "C212") (pin "1") (pinfunction "1_1") (pintype "passive"))
      (node (ref "IC5") (pin "AA29") (pinfunction "DIGPRVDD1_AA29") (pintype "power_in"))
      (node (ref "IC5") (pin "AE29") (pinfunction "DIGPRVDD1_AE29") (pintype "power_in"))
      (node (ref "IC5") (pin "L33") (pinfunction "DIGPRVDD1_L33") (pintype "power_in"))
      (node (ref "IC5") (pin "R31") (pinfunction "DIGPRVDD1_R31") (pintype "power_in"))
      (node (ref "R100") (pin "2") (pinfunction "2_2") (pintype "passive"))
      (node (ref "R99") (pin "2") (pinfunction "2_2") (pintype "passive"))
    )
    (net (code "3") (name "Net-(C228-Pad2)") (class "Default")
      (node (ref "C228") (pin "2") (pinfunction "2_2") (pintype "passive"))
      (node (ref "FR78") (pin "1") (pinfunction "1_1") (pintype "passive"))
      (node (ref "R101") (pin "2") (pinfunction "2_2") (pintype "passive"))
      (node (ref "R102") (pin "2") (pinfunction "2_2") (pintype "passive"))
    )
    (net (code "4") (name "Net-(C239-Pad1)") (class "Default")
      (node (ref "C239") (pin "1") (pinfunction "1_1") (pintype "passive"))
      (node (ref "C240") (pin "1") (pinfunction "1_1") (pintype "passive"))
      (node (ref "IC5") (pin "H32") (pinfunction "DIGPRVDD2_H32") (pintype "power_in"))
      (node (ref "R107") (pin "2") (pinfunction "2_2") (pintype "passive"))
    )
    (net (code "5") (name "Net-(C241-Pad1)") (class "Default")
      (node (ref "C241") (pin "1") (pinfunction "1_1") (pintype "passive"))
      (node (ref "C242") (pin "1") (pinfunction "1_1") (pintype "passive"))
      (node (ref "IC5") (pin "T32") (pinfunction "DIGPRVDD2_T32") (pintype "power_in"))
      (node (ref "R106") (pin "2") (pinfunction "2_2") (pintype "passive"))
    )
    (net (code "6") (name "Net-(C243-Pad1)") (class "Default")
      (node (ref "C243") (pin "1") (pinfunction "1_1") (pintype "passive"))
      (node (ref "C244") (pin "1") (pinfunction "1_1") (pintype "passive"))
      (node (ref "IC5") (pin "W33") (pinfunction "DIGPRVDD2_W33") (pintype "power_in"))
      (node (ref "R105") (pin "2") (pinfunction "2_2") (pintype "passive"))
    )
    (net (code "7") (name "Net-(C245-Pad1)") (class "Default")
      (node (ref "C245") (pin "1") (pinfunction "1_1") (pintype "passive"))
      (node (ref "C246") (pin "1") (pinfunction "1_1") (pintype "passive"))
      (node (ref "IC5") (pin "AH30") (pinfunction "DIGPRVDD2_AH30") (pintype "power_in"))
      (node (ref "R104") (pin "2") (pinfunction "2_2") (pintype "passive"))
    )
    (net (code "8") (name "Net-(C257-Pad1)") (class "Default")
      (node (ref "C257") (pin "1") (pinfunction "1_1") (pintype "passive"))
      (node (ref "FR99") (pin "2") (pinfunction "2_2") (pintype "passive"))
      (node (ref "R110") (pin "2") (pinfunction "2_2") (pintype "passive"))
    )
    (net (code "9") (name "Net-(C258-Pad1)") (class "Default")
      (node (ref "C258") (pin "1") (pinfunction "1_1") (pintype "passive"))
      (node (ref "FR98") (pin "1") (pinfunction "1_1") (pintype "passive"))
      (node (ref "R109") (pin "1") (pinfunction "1_1") (pintype "passive"))
    )
    (net (code "10") (name "Net-(IC5E-DIGPRPOC)") (class "Default")
      (node (ref "C237") (pin "1") (pinfunction "1_1") (pintype "passive"))
      (node (ref "C238") (pin "1") (pinfunction "1_1") (pintype "passive"))
      (node (ref "IC5") (pin "W31") (pinfunction "DIGPRPOC_W31") (pintype "power_in"))
      (node (ref "R108") (pin "2") (pinfunction "2_2") (pintype "passive"))
    )
    (net (code "11") (name "Net-(IC5E-VDD18_BIAS)") (class "Default")
      (node (ref "C250") (pin "1") (pinfunction "1_1") (pintype "passive"))
      (node (ref "FR95") (pin "1") (pinfunction "1_1") (pintype "passive"))
      (node (ref "IC5") (pin "E17") (pinfunction "VDD18_BIAS_E17") (pintype "power_in"))
    )
    (net (code "12") (name "Net-(IC5E-VDD18_DIG)") (class "Default")
      (node (ref "C235") (pin "1") (pinfunction "1_1") (pintype "passive"))
      (node (ref "IC5") (pin "D24") (pinfunction "VDD18_DIG_D24") (pintype "power_in"))
      (node (ref "R103") (pin "1") (pinfunction "1_1") (pintype "passive"))
    )
    (net (code "13") (name "Net-(IC5E-VDD18_LDO_RX)") (class "Default")
      (node (ref "C253") (pin "1") (pinfunction "1_1") (pintype "passive"))
      (node (ref "FR92") (pin "2") (pinfunction "2_2") (pintype "passive"))
      (node (ref "IC5") (pin "AE3") (pinfunction "VDD18_TIA_RFE_AE3") (pintype "power_in"))
      (node (ref "IC5") (pin "AF4") (pinfunction "VDD18_LDO_RX_AF4") (pintype "power_in"))
    )
    (net (code "14") (name "Net-(IC5E-VDD18_LDO_TX)") (class "Default")
      (node (ref "C254") (pin "1") (pinfunction "1_1") (pintype "passive"))
      (node (ref "FR91") (pin "2") (pinfunction "2_2") (pintype "passive"))
      (node (ref "IC5") (pin "N1") (pinfunction "VDD18_LDO_TX_N1") (pintype "power_in"))
    )
    (net (code "15") (name "Net-(IC5E-VDD18_RXBUF)") (class "Default")
      (node (ref "C255") (pin "1") (pinfunction "1_1") (pintype "passive"))
      (node (ref "FR99") (pin "1") (pinfunction "1_1") (pintype "passive"))
      (node (ref "IC5") (pin "AM26") (pinfunction "VDD18_RXBUF_AM26") (pintype "power_in"))
    )
    (net (code "16") (name "Net-(IC5E-VDD18_SXR)") (class "Default")
      (node (ref "C252") (pin "1") (pinfunction "1_1") (pintype "passive"))
      (node (ref "FR93") (pin "1") (pinfunction "1_1") (pintype "passive"))
      (node (ref "IC5") (pin "AM18") (pinfunction "VDD18_SXR_AM18") (pintype "power_in"))
    )
    (net (code "17") (name "Net-(IC5E-VDD18_TRF)") (class "Default")
      (node (ref "C249") (pin "1") (pinfunction "1_1") (pintype "passive"))
      (node (ref "FR96") (pin "1") (pinfunction "1_1") (pintype "passive"))
      (node (ref "IC5") (pin "D16") (pinfunction "VDD18_TRF_D16") (pintype "power_in"))
    )
    (net (code "18") (name "Net-(IC5E-VDD18_TXBUF)") (class "Default")
      (node (ref "C256") (pin "1") (pinfunction "1_1") (pintype "passive"))
      (node (ref "FR98") (pin "2") (pinfunction "2_2") (pintype "passive"))
      (node (ref "IC5") (pin "H6") (pinfunction "VDD18_TXBUF_H6") (pintype "power_in"))
    )
    (net (code "19") (name "Net-(IC5E-VDD18_VCO_CGEN)") (class "Default")
      (node (ref "C248") (pin "1") (pinfunction "1_1") (pintype "passive"))
      (node (ref "FR97") (pin "1") (pinfunction "1_1") (pintype "passive"))
      (node (ref "IC5") (pin "E21") (pinfunction "VDD18_VCO_CGEN_E21") (pintype "power_in"))
    )
    (net (code "20") (name "Net-(IC5E-VDD18_VCO_SXR)") (class "Default")
      (node (ref "C251") (pin "1") (pinfunction "1_1") (pintype "passive"))
      (node (ref "FR94") (pin "1") (pinfunction "1_1") (pintype "passive"))
      (node (ref "IC5") (pin "AK22") (pinfunction "VDD18_VCO_SXR_AK22") (pintype "power_in"))
    )
    (net (code "21") (name "Net-(IC5E-VDD18_VCO_SXT)") (class "Default")
      (node (ref "C247") (pin "1") (pinfunction "1_1") (pintype "passive"))
      (node (ref "FR90") (pin "1") (pinfunction "1_1") (pintype "passive"))
      (node (ref "IC5") (pin "G3") (pinfunction "VDD18_VCO_SXT_G3") (pintype "power_in"))
    )
    (net (code "22") (name "Net-(IC5F-DVDD_CGEN)") (class "Default")
      (node (ref "C202") (pin "1") (pinfunction "1_1") (pintype "passive"))
      (node (ref "C203") (pin "1") (pinfunction "1_1") (pintype "passive"))
      (node (ref "C204") (pin "1") (pinfunction "1_1") (pintype "passive"))
      (node (ref "FR69") (pin "1") (pinfunction "1_1") (pintype "passive"))
      (node (ref "IC5") (pin "A17") (pinfunction "DVDD_CGEN_A17") (pintype "power_in"))
      (node (ref "IC5") (pin "C25") (pinfunction "VDD12_DIG_C25") (pintype "power_in"))
      (node (ref "IC5") (pin "F24") (pinfunction "VDD_SPI_BUF_F24") (pintype "power_in"))
    )
    (net (code "23") (name "Net-(IC5F-DVDD_SXR)") (class "Default")
      (node (ref "C206") (pin "1") (pinfunction "1_1") (pintype "passive"))
      (node (ref "FR67") (pin "1") (pinfunction "1_1") (pintype "passive"))
      (node (ref "IC5") (pin "AL21") (pinfunction "DVDD_SXR_AL21") (pintype "power_in"))
    )
    (net (code "24") (name "Net-(IC5F-DVDD_SXT)") (class "Default")
      (node (ref "C205") (pin "2") (pinfunction "2_2") (pintype "passive"))
      (node (ref "FR68") (pin "1") (pinfunction "1_1") (pintype "passive"))
      (node (ref "IC5") (pin "M4") (pinfunction "DVDD_SXT_M4") (pintype "power_in"))
    )
    (net (code "25") (name "Net-(IC5F-VDD12O_VCO_SXT)") (class "Default")
      (node (ref "C227") (pin "2") (pinfunction "2_2") (pintype "passive"))
      (node (ref "FR70") (pin "1") (pinfunction "1_1") (pintype "passive"))
      (node (ref "IC5") (pin "J5") (pinfunction "VDD12O_VCO_SXT_J5") (pintype "power_in"))
      (node (ref "IC5") (pin "K6") (pinfunction "VDD12_VCO_SXT_K6") (pintype "power_in"))
    )
    (net (code "26") (name "Net-(IC5F-VDD12_LNA_RFE)") (class "Default")
      (node (ref "C224") (pin "1") (pinfunction "1_1") (pintype "passive"))
      (node (ref "FR74") (pin "1") (pinfunction "1_1") (pintype "passive"))
      (node (ref "IC5") (pin "AG5") (pinfunction "VDD12_LNA_RFE_AG5") (pintype "power_in"))
    )
    (net (code "27") (name "Net-(IC5F-VDD12_RXBUF)") (class "Default")
      (node (ref "C220") (pin "1") (pinfunction "1_1") (pintype "passive"))
      (node (ref "IC5") (pin "AP26") (pinfunction "VDD12_RXBUF_AP26") (pintype "power_in"))
      (node (ref "R102") (pin "1") (pinfunction "1_1") (pintype "passive"))
    )
    (net (code "28") (name "Net-(IC5F-VDD12_TIA_RFE)") (class "Default")
      (node (ref "C225") (pin "2") (pinfunction "2_2") (pintype "passive"))
      (node (ref "FR73") (pin "1") (pinfunction "1_1") (pintype "passive"))
      (node (ref "IC5") (pin "AD6") (pinfunction "VDD12_TIA_RFE_AD6") (pintype "power_in"))
    )
    (net (code "29") (name "Net-(IC5F-VDD12_TXBUF)") (class "Default")
      (node (ref "C213") (pin "1") (pinfunction "1_1") (pintype "passive"))
      (node (ref "IC5") (pin "G5") (pinfunction "VDD12_TXBUF_G5") (pintype "power_in"))
      (node (ref "R101") (pin "1") (pinfunction "1_1") (pintype "passive"))
    )
    (net (code "30") (name "Net-(IC5F-VDD12_VCO_SXR)") (class "Default")
      (node (ref "C221") (pin "1") (pinfunction "1_1") (pintype "passive"))
      (node (ref "FR77") (pin "1") (pinfunction "1_1") (pintype "passive"))
      (node (ref "IC5") (pin "AN23") (pinfunction "VDD12_VCO_SXR_AN23") (pintype "power_in"))
    )
    (net (code "31") (name "Net-(IC5F-VDD14_LNA_RFE)") (class "Default")
      (node (ref "C231") (pin "1") (pinfunction "1_1") (pintype "passive"))
      (node (ref "FR88") (pin "1") (pinfunction "1_1") (pintype "passive"))
      (node (ref "IC5") (pin "AF6") (pinfunction "VDD14_LNA_RFE_AF6") (pintype "power_in"))
    )
    (net (code "32") (name "Net-(IC5F-VDD14_RBB)") (class "Default")
      (node (ref "C233") (pin "1") (pinfunction "1_1") (pintype "passive"))
      (node (ref "FR86") (pin "1") (pinfunction "1_1") (pintype "passive"))
      (node (ref "IC5") (pin "AD4") (pinfunction "VDD14_RBB_AD4") (pintype "power_in"))
    )
    (net (code "33") (name "Net-(IC5F-VDD14_TIA_RFE)") (class "Default")
      (node (ref "C232") (pin "1") (pinfunction "1_1") (pintype "passive"))
      (node (ref "FR87") (pin "1") (pinfunction "1_1") (pintype "passive"))
      (node (ref "IC5") (pin "AF2") (pinfunction "VDD14_TIA_RFE_AF2") (pintype "power_in"))
    )
    (net (code "34") (name "Net-(IC5F-VDD14_VCO_CGEN)") (class "Default")
      (node (ref "C230") (pin "1") (pinfunction "1_1") (pintype "passive"))
      (node (ref "FR89") (pin "1") (pinfunction "1_1") (pintype "passive"))
      (node (ref "IC5") (pin "C21") (pinfunction "VDD14_VCO_CGEN_C21") (pintype "power_in"))
    )
    (net (code "35") (name "Net-(IC5F-VDDO_DIV_SXT)") (class "Default")
      (node (ref "C229") (pin "1") (pinfunction "1_1") (pintype "passive"))
      (node (ref "FR84") (pin "1") (pinfunction "1_1") (pintype "passive"))
      (node (ref "IC5") (pin "K2") (pinfunction "VDDO_DIV_SXT_K2") (pintype "power_in"))
      (node (ref "IC5") (pin "L5") (pinfunction "VDD_DIV_SXT_L5") (pintype "power_in"))
    )
    (net (code "36") (name "Net-(IC5F-VDDO_TLOBUF_TRF)") (class "Default")
      (node (ref "C215") (pin "1") (pinfunction "1_1") (pintype "passive"))
      (node (ref "FR83") (pin "1") (pinfunction "1_1") (pintype "passive"))
      (node (ref "IC5") (pin "D6") (pinfunction "VDDO_TLOBUF_TRF_D6") (pintype "power_in"))
      (node (ref "IC5") (pin "F8") (pinfunction "VDD_TLOBUF_TRF_F8") (pintype "power_in"))
    )
    (net (code "37") (name "Net-(IC5F-VDD_AFE)") (class "Default")
      (node (ref "C219") (pin "1") (pinfunction "1_1") (pintype "passive"))
      (node (ref "FR79") (pin "1") (pinfunction "1_1") (pintype "passive"))
      (node (ref "IC5") (pin "AJ25") (pinfunction "VDD_AFE_AJ25") (pintype "power_in"))
    )
    (net (code "38") (name "Net-(IC5F-VDD_CP_CGEN)") (class "Default")
      (node (ref "C218") (pin "2") (pinfunction "2_2") (pintype "passive"))
      (node (ref "FR80") (pin "1") (pinfunction "1_1") (pintype "passive"))
      (node (ref "IC5") (pin "F20") (pinfunction "VDD_CP_CGEN_F20") (pintype "power_in"))
    )
    (net (code "39") (name "Net-(IC5F-VDD_CP_SXR)") (class "Default")
      (node (ref "C223") (pin "1") (pinfunction "1_1") (pintype "passive"))
      (node (ref "FR75") (pin "1") (pinfunction "1_1") (pintype "passive"))
      (node (ref "IC5") (pin "AL19") (pinfunction "VDD_CP_SXR_AL19") (pintype "power_in"))
    )
    (net (code "40") (name "Net-(IC5F-VDD_CP_SXT)") (class "Default")
      (node (ref "C226") (pin "1") (pinfunction "1_1") (pintype "passive"))
      (node (ref "FR71") (pin "1") (pinfunction "1_1") (pintype "passive"))
      (node (ref "IC5") (pin "J3") (pinfunction "VDD_CP_SXT_J3") (pintype "power_in"))
    )
    (net (code "41") (name "Net-(IC5F-VDD_DIV_CGEN)") (class "Default")
      (node (ref "C217") (pin "1") (pinfunction "1_1") (pintype "passive"))
      (node (ref "FR81") (pin "1") (pinfunction "1_1") (pintype "passive"))
      (node (ref "IC5") (pin "E19") (pinfunction "VDD_DIV_CGEN_E19") (pintype "power_in"))
    )
    (net (code "42") (name "Net-(IC5F-VDD_DIV_SXR)") (class "Default")
      (node (ref "C222") (pin "1") (pinfunction "1_1") (pintype "passive"))
      (node (ref "FR76") (pin "1") (pinfunction "1_1") (pintype "passive"))
      (node (ref "IC5") (pin "AM20") (pinfunction "VDD_DIV_SXR_AM20") (pintype "power_in"))
    )
    (net (code "43") (name "Net-(IC5F-VDD_MXLOBUF_RFE)") (class "Default")
      (node (ref "C234") (pin "1") (pinfunction "1_1") (pintype "passive"))
      (node (ref "FR85") (pin "1") (pinfunction "1_1") (pintype "passive"))
      (node (ref "IC5") (pin "AN17") (pinfunction "VDD_MXLOBUF_RFE_AN17") (pintype "power_in"))
    )
    (net (code "44") (name "Net-(IC5F-VDD_TBB)") (class "Default")
      (node (ref "C214") (pin "1") (pinfunction "1_1") (pintype "passive"))
      (node (ref "FR72") (pin "1") (pinfunction "1_1") (pintype "passive"))
      (node (ref "IC5") (pin "P4") (pinfunction "VDD_TBB_P4") (pintype "power_in"))
    )
    (net (code "45") (name "Net-(IC5F-VDD_TPAD_TRF)") (class "Default")
      (node (ref "C216") (pin "1") (pinfunction "1_1") (pintype "passive"))
      (node (ref "FR82") (pin "1") (pinfunction "1_1") (pintype "passive"))
      (node (ref "IC5") (pin "B16") (pinfunction "VDD_TPAD_TRF_B16") (pintype "power_in"))
    )
    (net (code "46") (name "VCC1P4_LMS3") (class "Default")
      (node (ref "FR84") (pin "2") (pinfunction "2_2") (pintype "passive"))
      (node (ref "FR85") (pin "2") (pinfunction "2_2") (pintype "passive"))
      (node (ref "FR86") (pin "2") (pinfunction "2_2") (pintype "passive"))
      (node (ref "FR87") (pin "2") (pinfunction "2_2") (pintype "passive"))
      (node (ref "FR88") (pin "2") (pinfunction "2_2") (pintype "passive"))
      (node (ref "FR89") (pin "2") (pinfunction "2_2") (pintype "passive"))
      (node (ref "R99") (pin "1") (pinfunction "1_1") (pintype "passive"))
    )
    (net (code "47") (name "VCC1P8_LMS3") (class "Default")
      (node (ref "FR90") (pin "2") (pinfunction "2_2") (pintype "passive"))
      (node (ref "FR91") (pin "1") (pinfunction "1_1") (pintype "passive"))
      (node (ref "FR92") (pin "1") (pinfunction "1_1") (pintype "passive"))
      (node (ref "FR93") (pin "2") (pinfunction "2_2") (pintype "passive"))
      (node (ref "FR94") (pin "2") (pinfunction "2_2") (pintype "passive"))
      (node (ref "FR95") (pin "2") (pinfunction "2_2") (pintype "passive"))
      (node (ref "FR96") (pin "2") (pinfunction "2_2") (pintype "passive"))
      (node (ref "FR97") (pin "2") (pinfunction "2_2") (pintype "passive"))
      (node (ref "R103") (pin "2") (pinfunction "2_2") (pintype "passive"))
      (node (ref "R109") (pin "2") (pinfunction "2_2") (pintype "passive"))
      (node (ref "R110") (pin "1") (pinfunction "1_1") (pintype "passive"))
    )
    (net (code "48") (name "VCC1P25_LMS3") (class "Default")
      (node (ref "FR67") (pin "2") (pinfunction "2_2") (pintype "passive"))
      (node (ref "FR68") (pin "2") (pinfunction "2_2") (pintype "passive"))
      (node (ref "FR69") (pin "2") (pinfunction "2_2") (pintype "passive"))
      (node (ref "FR70") (pin "2") (pinfunction "2_2") (pintype "passive"))
      (node (ref "FR71") (pin "2") (pinfunction "2_2") (pintype "passive"))
      (node (ref "FR72") (pin "2") (pinfunction "2_2") (pintype "passive"))
      (node (ref "FR73") (pin "2") (pinfunction "2_2") (pintype "passive"))
      (node (ref "FR74") (pin "2") (pinfunction "2_2") (pintype "passive"))
      (node (ref "FR75") (pin "2") (pinfunction "2_2") (pintype "passive"))
      (node (ref "FR76") (pin "2") (pinfunction "2_2") (pintype "passive"))
      (node (ref "FR77") (pin "2") (pinfunction "2_2") (pintype "passive"))
      (node (ref "FR78") (pin "2") (pinfunction "2_2") (pintype "passive"))
      (node (ref "FR79") (pin "2") (pinfunction "2_2") (pintype "passive"))
      (node (ref "FR80") (pin "2") (pinfunction "2_2") (pintype "passive"))
      (node (ref "FR81") (pin "2") (pinfunction "2_2") (pintype "passive"))
      (node (ref "FR82") (pin "2") (pinfunction "2_2") (pintype "passive"))
      (node (ref "FR83") (pin "2") (pinfunction "2_2") (pintype "passive"))
      (node (ref "R100") (pin "1") (pinfunction "1_1") (pintype "passive"))
    )
    (net (code "49") (name "VDIO_LMS") (class "Default")
      (node (ref "C236") (pin "2") (pinfunction "2_2") (pintype "passive"))
      (node (ref "R104") (pin "1") (pinfunction "1_1") (pintype "passive"))
      (node (ref "R105") (pin "1") (pinfunction "1_1") (pintype "passive"))
      (node (ref "R106") (pin "1") (pinfunction "1_1") (pintype "passive"))
      (node (ref "R107") (pin "1") (pinfunction "1_1") (pintype "passive"))
      (node (ref "R108") (pin "1") (pinfunction "1_1") (pintype "passive"))
    )
  )
)
